# munia-n64.net
KiCad netlist of a schematic drawn in EAGLE
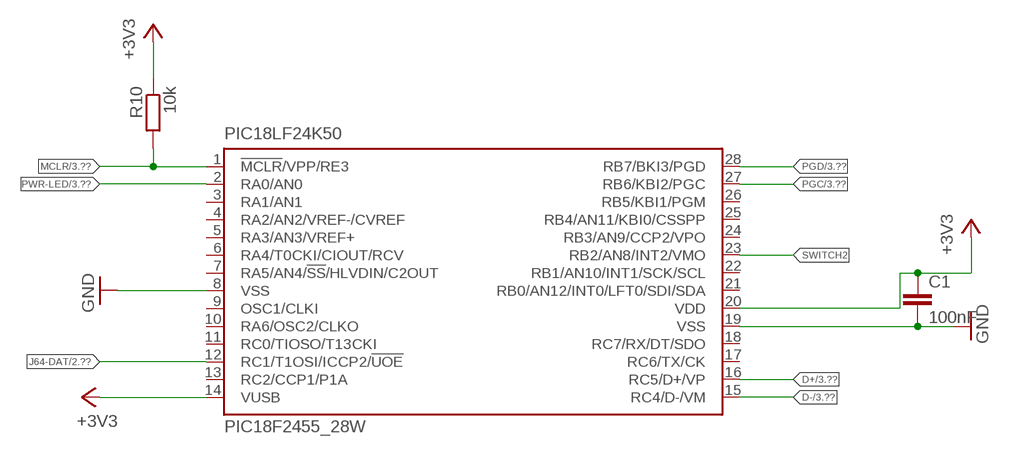
[diagram p0: schematic, sheet 1]
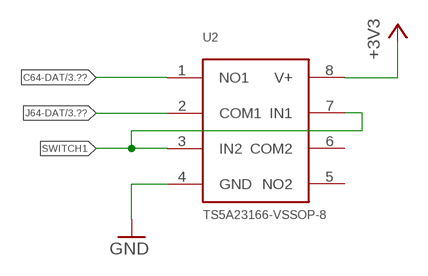
[diagram p1: schematic, sheet 2]
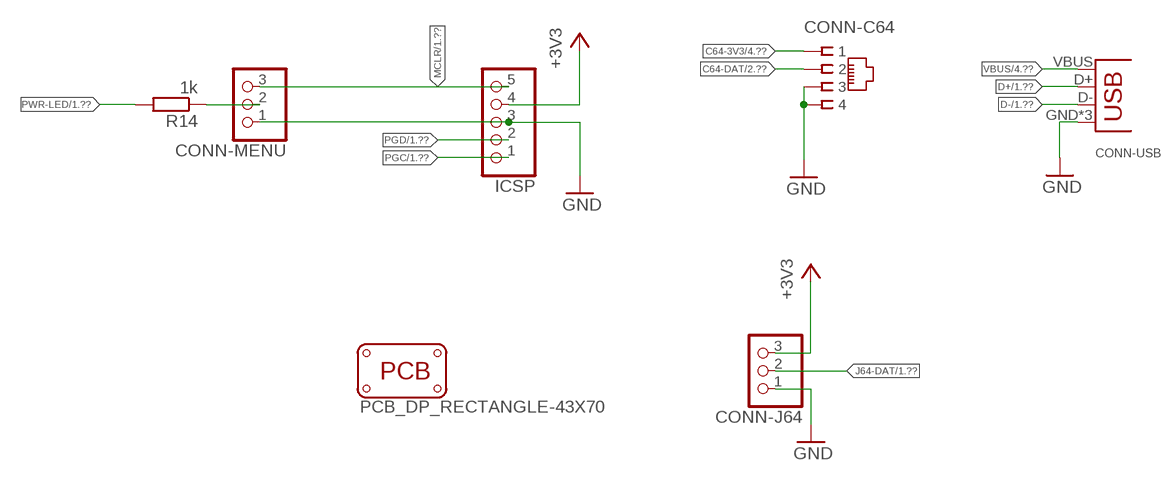
[diagram p2: schematic, sheet 3]
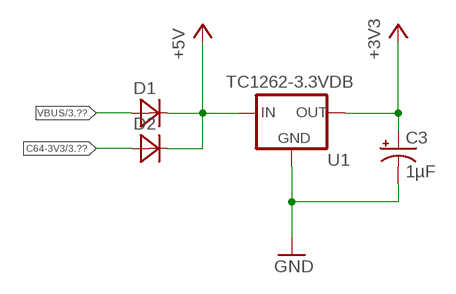
[diagram p3: schematic, sheet 4]

(export (version "E")
  (design (tool "Eeschema 10.0.6"))
  (components
    (comp (ref "C1")
      (value "100nF")
      (footprint "eagle-import:C0603")
      (libsource (lib "eagle-import") (part "C-EUC0603"))
    )
    (comp (ref "PIC18LF24K50")
      (value "PIC18F2455_28W")
      (footprint "eagle-import:SO28W")
      (fields (field (name "MF") "MICROCHIP") (field (name "MPN") "PIC18F2455-I/SO"))
      (libsource (lib "eagle-import") (part "PIC18F2_28W455"))
    )
    (comp (ref "R10")
      (value "10k")
      (footprint "eagle-import:R0603")
      (libsource (lib "eagle-import") (part "R-EU_R0603"))
    )
    (comp (ref "U2")
      (value "TS5A23166-VSSOP-8")
      (footprint "eagle-import:SOT765")
      (libsource (lib "eagle-import") (part "TS5A23166-VSSOP-8"))
    )
    (comp (ref "CONN-C64")
      (value "RJ11-6P4C")
      (footprint "eagle-import:RJ11-4C")
      (libsource (lib "eagle-import") (part "RJ11-6P4C"))
    )
    (comp (ref "CONN-J64")
      (value "PINHD-1X3")
      (footprint "eagle-import:1X03")
      (libsource (lib "eagle-import") (part "PINHD-1X3"))
    )
    (comp (ref "CONN-MENU")
      (value "PINHD-1X3")
      (footprint "eagle-import:1X03")
      (libsource (lib "eagle-import") (part "PINHD-1X3"))
    )
    (comp (ref "CONN-USB")
      (value "USB-B-NIELS")
      (footprint "eagle-import:USB-B-H")
      (libsource (lib "eagle-import") (part "USB-B-NIELS"))
    )
    (comp (ref "ICSP")
      (value "PINHD-1X5")
      (footprint "eagle-import:1X05")
      (libsource (lib "eagle-import") (part "PINHD-1X5"))
    )
    (comp (ref "PCB1")
      (value "PCB_DP_RECTANGLE-43X70")
      (footprint "eagle-import:DP7043_V1")
      (libsource (lib "eagle-import") (part "PCB_DP_RECTANGLE-43X70"))
    )
    (comp (ref "R14")
      (value "1k")
      (footprint "eagle-import:R0603")
      (libsource (lib "eagle-import") (part "R-EU_R0603"))
    )
    (comp (ref "C3")
      (value "1µF")
      (footprint "eagle-import:EIA3216")
      (libsource (lib "eagle-import") (part "TANT-CAP1206"))
    )
    (comp (ref "D1")
      (value "MBR120VLSFT1G")
      (footprint "eagle-import:SOD123")
      (libsource (lib "eagle-import") (part "MBR120VLSFT1G"))
    )
    (comp (ref "D2")
      (value "MBR120VLSFT1G")
      (footprint "eagle-import:SOD123")
      (libsource (lib "eagle-import") (part "MBR120VLSFT1G"))
    )
    (comp (ref "U1")
      (value "TC1262-3.3VDB")
      (footprint "eagle-import:SOT230P700X180-4N")
      (libsource (lib "eagle-import") (part "TC1262-3.3VDB"))
    )
  )
  (nets
    (net (code "1") (name "+3V3") (class "Default")
      (node (ref "C1") (pin "1") (pinfunction "1_1") (pintype "passive"))
      (node (ref "C3") (pin "A") (pinfunction "+_A") (pintype "passive"))
      (node (ref "CONN-J64") (pin "3") (pinfunction "3_3") (pintype "passive"))
      (node (ref "ICSP") (pin "4") (pinfunction "4_4") (pintype "passive"))
      (node (ref "PIC18LF24K50") (pin "14") (pinfunction "VUSB_14") (pintype "bidirectional"))
      (node (ref "PIC18LF24K50") (pin "20") (pinfunction "VDD_20") (pintype "power_in"))
      (node (ref "R10") (pin "1") (pinfunction "1_1") (pintype "passive"))
      (node (ref "U1") (pin "3") (pinfunction "OUT_3") (pintype "passive"))
      (node (ref "U2") (pin "8") (pinfunction "V+_8") (pintype "bidirectional"))
    )
    (net (code "2") (name "+5V") (class "Default")
      (node (ref "D1") (pin "1") (pinfunction "C_1") (pintype "passive"))
      (node (ref "D2") (pin "1") (pinfunction "C_1") (pintype "passive"))
      (node (ref "U1") (pin "1") (pinfunction "IN_1") (pintype "input"))
    )
    (net (code "3") (name "C64-3V3") (class "Default")
      (node (ref "CONN-C64") (pin "1") (pinfunction "1_1") (pintype "passive"))
      (node (ref "D2") (pin "2") (pinfunction "A_2") (pintype "passive"))
    )
    (net (code "4") (name "C64-DAT") (class "Default")
      (node (ref "CONN-C64") (pin "2") (pinfunction "2_2") (pintype "passive"))
      (node (ref "U2") (pin "1") (pinfunction "NO1_1") (pintype "bidirectional"))
    )
    (net (code "5") (name "D+") (class "Default")
      (node (ref "CONN-USB") (pin "D+") (pinfunction "D+_D+") (pintype "bidirectional"))
      (node (ref "PIC18LF24K50") (pin "16") (pinfunction "RC5/D+/VP_16") (pintype "bidirectional"))
    )
    (net (code "6") (name "D-") (class "Default")
      (node (ref "CONN-USB") (pin "D-") (pinfunction "D-_D-") (pintype "bidirectional"))
      (node (ref "PIC18LF24K50") (pin "15") (pinfunction "RC4/D-/VM_15") (pintype "bidirectional"))
    )
    (net (code "7") (name "GND") (class "Default")
      (node (ref "C1") (pin "2") (pinfunction "2_2") (pintype "passive"))
      (node (ref "C3") (pin "C") (pinfunction "-_C") (pintype "passive"))
      (node (ref "CONN-C64") (pin "3") (pinfunction "3_3") (pintype "passive"))
      (node (ref "CONN-C64") (pin "4") (pinfunction "4_4") (pintype "passive"))
      (node (ref "CONN-J64") (pin "1") (pinfunction "1_1") (pintype "passive"))
      (node (ref "CONN-MENU") (pin "1") (pinfunction "1_1") (pintype "passive"))
      (node (ref "CONN-USB") (pin "GND") (pinfunction "GND_GND") (pintype "bidirectional"))
      (node (ref "CONN-USB") (pin "GND@1") (pinfunction "GND_GND@1") (pintype "bidirectional"))
      (node (ref "CONN-USB") (pin "GND@2") (pinfunction "GND_GND@2") (pintype "bidirectional"))
      (node (ref "ICSP") (pin "3") (pinfunction "3_3") (pintype "passive"))
      (node (ref "PIC18LF24K50") (pin "19") (pinfunction "VSS_19") (pintype "power_in"))
      (node (ref "PIC18LF24K50") (pin "8") (pinfunction "VSS_8") (pintype "power_in"))
      (node (ref "U1") (pin "2") (pinfunction "GND_2") (pintype "input"))
      (node (ref "U1") (pin "4") (pinfunction "GND_4") (pintype "input"))
      (node (ref "U2") (pin "4") (pinfunction "GND_4") (pintype "bidirectional"))
    )
    (net (code "8") (name "J64-DAT") (class "Default")
      (node (ref "CONN-J64") (pin "2") (pinfunction "2_2") (pintype "passive"))
      (node (ref "PIC18LF24K50") (pin "12") (pinfunction "RC1/T1OSI/ICCP2/~{UOE}_12") (pintype "bidirectional"))
      (node (ref "U2") (pin "2") (pinfunction "COM1_2") (pintype "bidirectional"))
    )
    (net (code "9") (name "MCLR") (class "Default")
      (node (ref "CONN-MENU") (pin "3") (pinfunction "3_3") (pintype "passive"))
      (node (ref "ICSP") (pin "5") (pinfunction "5_5") (pintype "passive"))
      (node (ref "PIC18LF24K50") (pin "1") (pinfunction "~{MCLR}/VPP/RE3_1") (pintype "input"))
      (node (ref "R10") (pin "2") (pinfunction "2_2") (pintype "passive"))
    )
    (net (code "10") (name "Net-(CONN-MENU-Pad2)") (class "Default")
      (node (ref "CONN-MENU") (pin "2") (pinfunction "2_2") (pintype "passive"))
      (node (ref "R14") (pin "1") (pinfunction "1_1") (pintype "passive"))
    )
    (net (code "11") (name "PGC") (class "Default")
      (node (ref "ICSP") (pin "1") (pinfunction "1_1") (pintype "passive"))
      (node (ref "PIC18LF24K50") (pin "27") (pinfunction "RB6/KBI2/PGC_27") (pintype "bidirectional"))
    )
    (net (code "12") (name "PGD") (class "Default")
      (node (ref "ICSP") (pin "2") (pinfunction "2_2") (pintype "passive"))
      (node (ref "PIC18LF24K50") (pin "28") (pinfunction "RB7/BKI3/PGD_28") (pintype "bidirectional"))
    )
    (net (code "13") (name "PWR-LED") (class "Default")
      (node (ref "PIC18LF24K50") (pin "2") (pinfunction "RA0/AN0_2") (pintype "bidirectional"))
      (node (ref "R14") (pin "2") (pinfunction "2_2") (pintype "passive"))
    )
    (net (code "14") (name "SWITCH1") (class "Default")
      (node (ref "U2") (pin "3") (pinfunction "IN2_3") (pintype "bidirectional"))
      (node (ref "U2") (pin "7") (pinfunction "IN1_7") (pintype "bidirectional"))
    )
    (net (code "15") (name "SWITCH2") (class "Default")
      (node (ref "PIC18LF24K50") (pin "23") (pinfunction "RB2/AN8/INT2/VMO_23") (pintype "bidirectional"))
    )
    (net (code "16") (name "VBUS") (class "Default")
      (node (ref "CONN-USB") (pin "VBUS") (pinfunction "VBUS_VBUS") (pintype "bidirectional"))
      (node (ref "D1") (pin "2") (pinfunction "A_2") (pintype "passive"))
    )
    (net (code "17") (name "unconnected-(PIC18LF24K50-OSC1{slash}CLKI-Pad9)") (class "Default")
      (node (ref "PIC18LF24K50") (pin "9") (pinfunction "OSC1/CLKI_9") (pintype "input"))
    )
    (net (code "18") (name "unconnected-(PIC18LF24K50-RA1{slash}AN1-Pad3)") (class "Default")
      (node (ref "PIC18LF24K50") (pin "3") (pinfunction "RA1/AN1_3") (pintype "bidirectional"))
    )
    (net (code "19") (name "unconnected-(PIC18LF24K50-RA2{slash}AN2{slash}VREF-{slash}CVREF-Pad4)") (class "Default")
      (node (ref "PIC18LF24K50") (pin "4") (pinfunction "RA2/AN2/VREF-/CVREF_4") (pintype "bidirectional"))
    )
    (net (code "20") (name "unconnected-(PIC18LF24K50-RA3{slash}AN3{slash}VREF+-Pad5)") (class "Default")
      (node (ref "PIC18LF24K50") (pin "5") (pinfunction "RA3/AN3/VREF+_5") (pintype "bidirectional"))
    )
    (net (code "21") (name "unconnected-(PIC18LF24K50-RA4{slash}T0CKI{slash}CIOUT{slash}RCV-Pad6)") (class "Default")
      (node (ref "PIC18LF24K50") (pin "6") (pinfunction "RA4/T0CKI/CIOUT/RCV_6") (pintype "bidirectional"))
    )
    (net (code "22") (name "unconnected-(PIC18LF24K50-RA5{slash}AN4{slash}~{SS}{slash}HLVDIN{slash}C2OUT-Pad7)") (class "Default")
      (node (ref "PIC18LF24K50") (pin "7") (pinfunction "RA5/AN4/~{SS}/HLVDIN/C2OUT_7") (pintype "bidirectional"))
    )
    (net (code "23") (name "unconnected-(PIC18LF24K50-RA6{slash}OSC2{slash}CLKO-Pad10)") (class "Default")
      (node (ref "PIC18LF24K50") (pin "10") (pinfunction "RA6/OSC2/CLKO_10") (pintype "output"))
    )
    (net (code "24") (name "unconnected-(PIC18LF24K50-RB0{slash}AN12{slash}INT0{slash}LFT0{slash}SDI{slash}SDA-Pad21)") (class "Default")
      (node (ref "PIC18LF24K50") (pin "21") (pinfunction "RB0/AN12/INT0/LFT0/SDI/SDA_21") (pintype "bidirectional"))
    )
    (net (code "25") (name "unconnected-(PIC18LF24K50-RB1{slash}AN10{slash}INT1{slash}SCK{slash}SCL-Pad22)") (class "Default")
      (node (ref "PIC18LF24K50") (pin "22") (pinfunction "RB1/AN10/INT1/SCK/SCL_22") (pintype "bidirectional"))
    )
    (net (code "26") (name "unconnected-(PIC18LF24K50-RB3{slash}AN9{slash}CCP2{slash}VPO-Pad24)") (class "Default")
      (node (ref "PIC18LF24K50") (pin "24") (pinfunction "RB3/AN9/CCP2/VPO_24") (pintype "bidirectional"))
    )
    (net (code "27") (name "unconnected-(PIC18LF24K50-RB4{slash}AN11{slash}KBI0{slash}CSSPP-Pad25)") (class "Default")
      (node (ref "PIC18LF24K50") (pin "25") (pinfunction "RB4/AN11/KBI0/CSSPP_25") (pintype "bidirectional"))
    )
    (net (code "28") (name "unconnected-(PIC18LF24K50-RB5{slash}KBI1{slash}PGM-Pad26)") (class "Default")
      (node (ref "PIC18LF24K50") (pin "26") (pinfunction "RB5/KBI1/PGM_26") (pintype "bidirectional"))
    )
    (net (code "29") (name "unconnected-(PIC18LF24K50-RC0{slash}TIOSO{slash}T13CKI-Pad11)") (class "Default")
      (node (ref "PIC18LF24K50") (pin "11") (pinfunction "RC0/TIOSO/T13CKI_11") (pintype "bidirectional"))
    )
    (net (code "30") (name "unconnected-(PIC18LF24K50-RC2{slash}CCP1{slash}P1A-Pad13)") (class "Default")
      (node (ref "PIC18LF24K50") (pin "13") (pinfunction "RC2/CCP1/P1A_13") (pintype "bidirectional"))
    )
    (net (code "31") (name "unconnected-(PIC18LF24K50-RC6{slash}TX{slash}CK-Pad17)") (class "Default")
      (node (ref "PIC18LF24K50") (pin "17") (pinfunction "RC6/TX/CK_17") (pintype "bidirectional"))
    )
    (net (code "32") (name "unconnected-(PIC18LF24K50-RC7{slash}RX{slash}DT{slash}SDO-Pad18)") (class "Default")
      (node (ref "PIC18LF24K50") (pin "18") (pinfunction "RC7/RX/DT/SDO_18") (pintype "bidirectional"))
    )
    (net (code "33") (name "unconnected-(U2-COM2-Pad6)") (class "Default")
      (node (ref "U2") (pin "6") (pinfunction "COM2_6") (pintype "bidirectional"))
    )
    (net (code "34") (name "unconnected-(U2-NO2-Pad5)") (class "Default")
      (node (ref "U2") (pin "5") (pinfunction "NO2_5") (pintype "bidirectional"))
    )
  )
)
